# simreader_marble.net
KiCad netlist of a schematic drawn in EAGLE
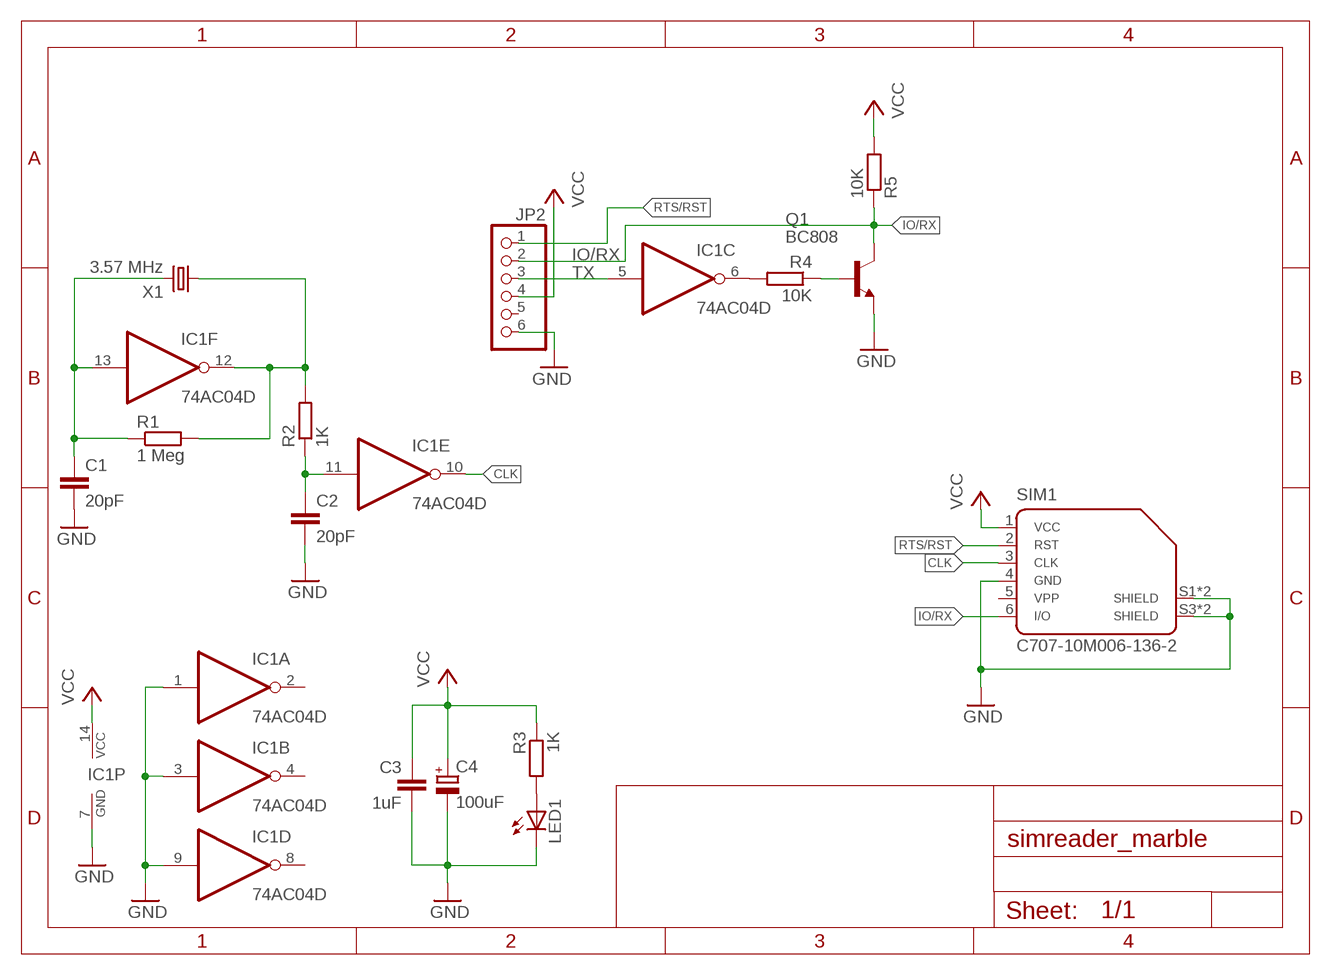
[diagram p0: schematic, sheet 1]

(export (version "E")
  (design (tool "Eeschema 10.0.6"))
  (components
    (comp (ref "C1")
      (value "20pF")
      (footprint "eagle-import:C0603")
      (libsource (lib "eagle-import") (part "C-EUC0603"))
    )
    (comp (ref "C2")
      (value "20pF")
      (footprint "eagle-import:C0603")
      (libsource (lib "eagle-import") (part "C-EUC0603"))
    )
    (comp (ref "C3")
      (value "1uF")
      (footprint "eagle-import:C0603")
      (libsource (lib "eagle-import") (part "C-EUC0603"))
    )
    (comp (ref "C4")
      (value "100uF")
      (footprint "eagle-import:140CLH-0810")
      (libsource (lib "eagle-import") (part "CPOL-EU140CLH-0810"))
    )
    (comp (ref "IC1")
      (value "74AC04D")
      (footprint "eagle-import:SO14")
      (libsource (lib "eagle-import") (part "7404DAC"))
    )
    (comp (ref "JP2")
      (value "PINHD-1X6")
      (footprint "eagle-import:1X06")
      (libsource (lib "eagle-import") (part "PINHD-1X6"))
    )
    (comp (ref "LED1")
      (value "LEDCHIPLED_0603")
      (footprint "eagle-import:CHIPLED_0603")
      (libsource (lib "eagle-import") (part "LEDCHIPLED_0603"))
    )
    (comp (ref "Q1")
      (value "BC808")
      (footprint "eagle-import:SOT23-BEC")
      (libsource (lib "eagle-import") (part "-NPN-SOT23-BECBC808"))
    )
    (comp (ref "R1")
      (value "1 Meg")
      (footprint "eagle-import:R0603")
      (libsource (lib "eagle-import") (part "R-EU_R0603"))
    )
    (comp (ref "R2")
      (value "1K")
      (footprint "eagle-import:R0603")
      (libsource (lib "eagle-import") (part "R-EU_R0603"))
    )
    (comp (ref "R3")
      (value "1K")
      (footprint "eagle-import:R0603")
      (libsource (lib "eagle-import") (part "R-EU_R0603"))
    )
    (comp (ref "R4")
      (value "10K")
      (footprint "eagle-import:R0603")
      (libsource (lib "eagle-import") (part "R-EU_R0603"))
    )
    (comp (ref "R5")
      (value "10K")
      (footprint "eagle-import:R0603")
      (libsource (lib "eagle-import") (part "R-EU_R0603"))
    )
    (comp (ref "SIM1")
      (value "C707-10M006-136-2")
      (footprint "eagle-import:C707_10M006_136_2")
      (libsource (lib "eagle-import") (part "C707-10M006-136-2"))
    )
    (comp (ref "X1")
      (value "3.57 MHz")
      (footprint "eagle-import:HC49UP")
      (libsource (lib "eagle-import") (part "CRYSTALHC49UP"))
    )
  )
  (nets
    (net (code "1") (name "/TX") (class "Default")
      (node (ref "IC1") (pin "5") (pinfunction "I_5") (pintype "input"))
      (node (ref "JP2") (pin "3") (pinfunction "3_3") (pintype "passive"))
    )
    (net (code "2") (name "CLK") (class "Default")
      (node (ref "IC1") (pin "10") (pinfunction "O_10") (pintype "output"))
      (node (ref "SIM1") (pin "3") (pinfunction "3_3") (pintype "passive"))
    )
    (net (code "3") (name "GND") (class "Default")
      (node (ref "C1") (pin "2") (pinfunction "2_2") (pintype "passive"))
      (node (ref "C2") (pin "2") (pinfunction "2_2") (pintype "passive"))
      (node (ref "C3") (pin "2") (pinfunction "2_2") (pintype "passive"))
      (node (ref "C4") (pin "-") (pinfunction "-_-") (pintype "passive"))
      (node (ref "IC1") (pin "1") (pinfunction "I_1") (pintype "input"))
      (node (ref "IC1") (pin "3") (pinfunction "I_3") (pintype "input"))
      (node (ref "IC1") (pin "7") (pinfunction "GND_7") (pintype "power_in"))
      (node (ref "IC1") (pin "9") (pinfunction "I_9") (pintype "input"))
      (node (ref "JP2") (pin "6") (pinfunction "6_6") (pintype "passive"))
      (node (ref "LED1") (pin "C") (pinfunction "C_C") (pintype "passive"))
      (node (ref "Q1") (pin "E") (pinfunction "E_E") (pintype "passive"))
      (node (ref "SIM1") (pin "4") (pinfunction "4_4") (pintype "passive"))
      (node (ref "SIM1") (pin "S1") (pinfunction "S1_S1") (pintype "passive"))
      (node (ref "SIM1") (pin "S2") (pinfunction "S1_S2") (pintype "passive"))
      (node (ref "SIM1") (pin "S3") (pinfunction "S2_S3") (pintype "passive"))
      (node (ref "SIM1") (pin "S4") (pinfunction "S2_S4") (pintype "passive"))
    )
    (net (code "4") (name "IO{slash}RX") (class "Default")
      (node (ref "JP2") (pin "2") (pinfunction "2_2") (pintype "passive"))
      (node (ref "Q1") (pin "C") (pinfunction "C_C") (pintype "passive"))
      (node (ref "R5") (pin "1") (pinfunction "1_1") (pintype "passive"))
      (node (ref "SIM1") (pin "6") (pinfunction "6_6") (pintype "passive"))
    )
    (net (code "5") (name "Net-(IC1C-O)") (class "Default")
      (node (ref "IC1") (pin "6") (pinfunction "O_6") (pintype "output"))
      (node (ref "R4") (pin "2") (pinfunction "2_2") (pintype "passive"))
    )
    (net (code "6") (name "Net-(IC1E-I)") (class "Default")
      (node (ref "C2") (pin "1") (pinfunction "1_1") (pintype "passive"))
      (node (ref "IC1") (pin "11") (pinfunction "I_11") (pintype "input"))
      (node (ref "R2") (pin "1") (pinfunction "1_1") (pintype "passive"))
    )
    (net (code "7") (name "Net-(IC1F-I)") (class "Default")
      (node (ref "C1") (pin "1") (pinfunction "1_1") (pintype "passive"))
      (node (ref "IC1") (pin "13") (pinfunction "I_13") (pintype "input"))
      (node (ref "R1") (pin "1") (pinfunction "1_1") (pintype "passive"))
      (node (ref "X1") (pin "2") (pinfunction "2_2") (pintype "passive"))
    )
    (net (code "8") (name "Net-(IC1F-O)") (class "Default")
      (node (ref "IC1") (pin "12") (pinfunction "O_12") (pintype "output"))
      (node (ref "R1") (pin "2") (pinfunction "2_2") (pintype "passive"))
      (node (ref "R2") (pin "2") (pinfunction "2_2") (pintype "passive"))
      (node (ref "X1") (pin "1") (pinfunction "1_1") (pintype "passive"))
    )
    (net (code "9") (name "Net-(LED1-PadA)") (class "Default")
      (node (ref "LED1") (pin "A") (pinfunction "A_A") (pintype "passive"))
      (node (ref "R3") (pin "2") (pinfunction "2_2") (pintype "passive"))
    )
    (net (code "10") (name "Net-(Q1-PadB)") (class "Default")
      (node (ref "Q1") (pin "B") (pinfunction "B_B") (pintype "passive"))
      (node (ref "R4") (pin "1") (pinfunction "1_1") (pintype "passive"))
    )
    (net (code "11") (name "RTS{slash}RST") (class "Default")
      (node (ref "JP2") (pin "1") (pinfunction "1_1") (pintype "passive"))
      (node (ref "SIM1") (pin "2") (pinfunction "2_2") (pintype "passive"))
    )
    (net (code "12") (name "VCC") (class "Default")
      (node (ref "C3") (pin "1") (pinfunction "1_1") (pintype "passive"))
      (node (ref "C4") (pin "+") (pinfunction "+_+") (pintype "passive"))
      (node (ref "IC1") (pin "14") (pinfunction "VCC_14") (pintype "power_in"))
      (node (ref "JP2") (pin "4") (pinfunction "4_4") (pintype "passive"))
      (node (ref "R3") (pin "1") (pinfunction "1_1") (pintype "passive"))
      (node (ref "R5") (pin "2") (pinfunction "2_2") (pintype "passive"))
      (node (ref "SIM1") (pin "1") (pinfunction "1_1") (pintype "passive"))
    )
    (net (code "13") (name "unconnected-(IC1A-O-Pad2)") (class "Default")
      (node (ref "IC1") (pin "2") (pinfunction "O_2") (pintype "output"))
    )
    (net (code "14") (name "unconnected-(IC1B-O-Pad4)") (class "Default")
      (node (ref "IC1") (pin "4") (pinfunction "O_4") (pintype "output"))
    )
    (net (code "15") (name "unconnected-(IC1D-O-Pad8)") (class "Default")
      (node (ref "IC1") (pin "8") (pinfunction "O_8") (pintype "output"))
    )
    (net (code "16") (name "unconnected-(JP2-Pad5)") (class "Default")
      (node (ref "JP2") (pin "5") (pinfunction "5_5") (pintype "passive"))
    )
    (net (code "17") (name "unconnected-(SIM1-Pad5)") (class "Default")
      (node (ref "SIM1") (pin "5") (pinfunction "5_5") (pintype "passive"))
    )
  )
)
